# DAQ_IO.net
KiCad netlist of a schematic drawn in Altium Designer
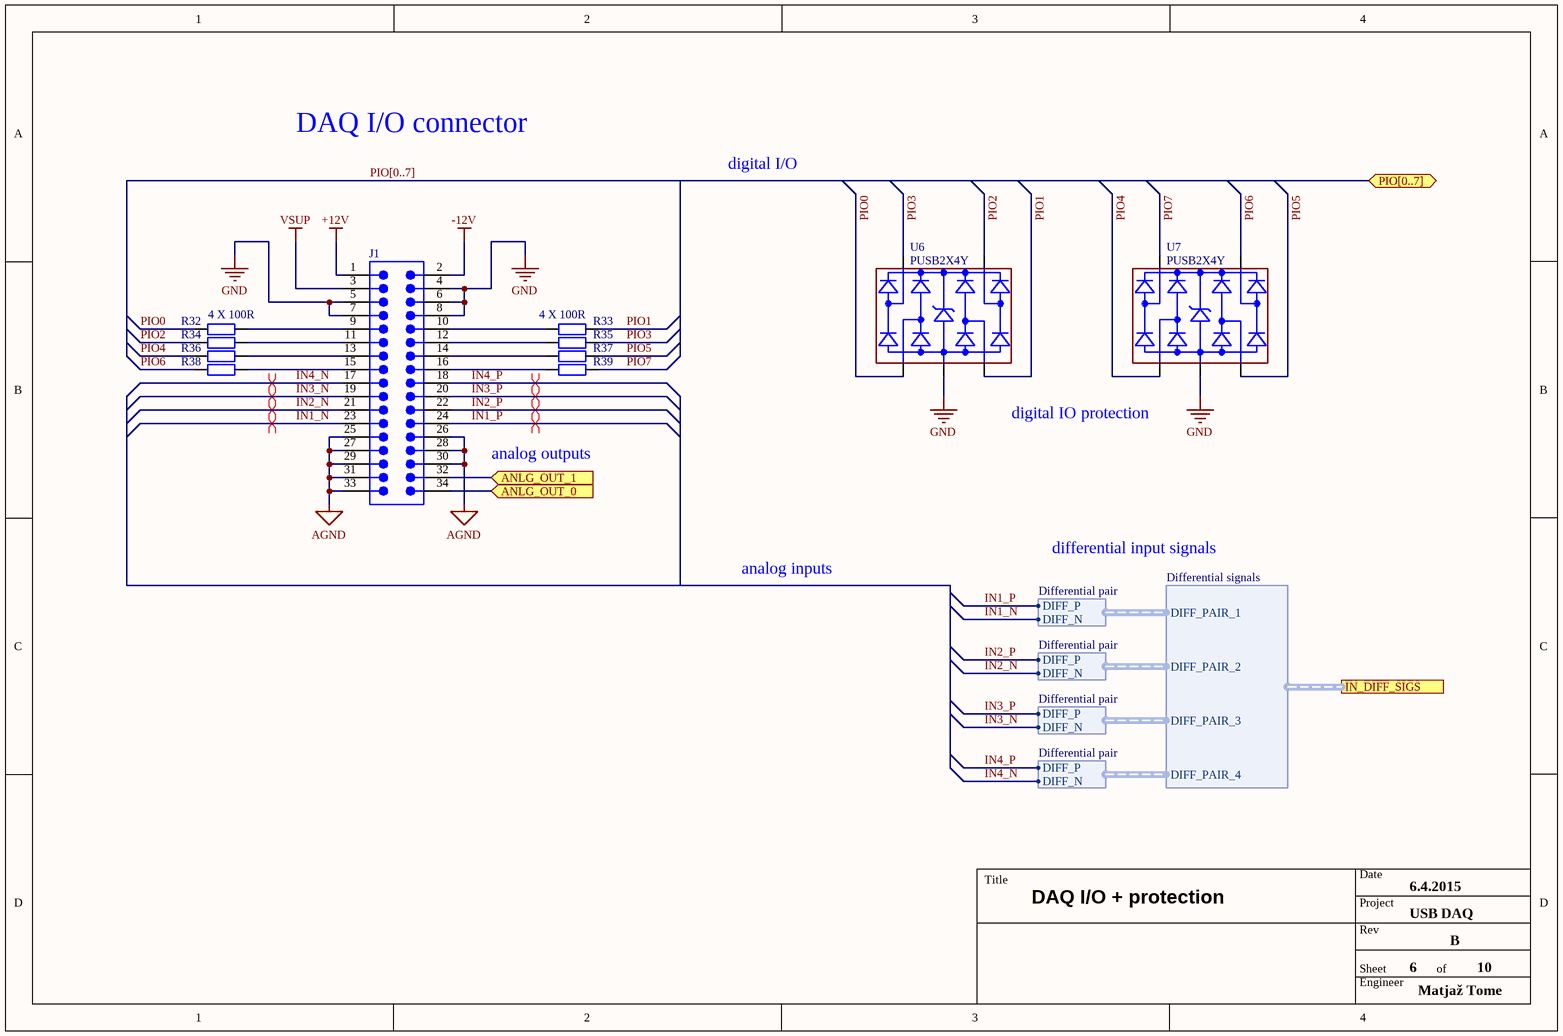
[diagram p0: DAQ_IO.SchDoc]

(export (version "E")
  (design (tool "Eeschema 10.0.6"))
  (components
    (comp (ref "J1")
      (value "2X17")
      (footprint "IDC34R")
      (description "Pin Header, Right Angle, Wire-to-Board, 2.54 mm, 2 Rows, 34 Contacts, Through Hole Right Angle")
      (fields (field (name "MANUFACTURER") "Harting"))
      (libsource (lib "DAQ_REV_B") (part "09 18 534 7323"))
    )
    (comp (ref "R32")
      (value "100R")
      (footprint "R_0603")
      (description "Generic resistor")
      (libsource (lib "DAQ_REV_B") (part "Resistor"))
    )
    (comp (ref "R33")
      (value "100R")
      (footprint "R_0603")
      (description "Generic resistor")
      (libsource (lib "DAQ_REV_B") (part "Resistor"))
    )
    (comp (ref "R34")
      (value "100R")
      (footprint "R_0603")
      (description "Generic resistor")
      (libsource (lib "DAQ_REV_B") (part "Resistor"))
    )
    (comp (ref "R35")
      (value "100R")
      (footprint "R_0603")
      (description "Generic resistor")
      (libsource (lib "DAQ_REV_B") (part "Resistor"))
    )
    (comp (ref "R36")
      (value "100R")
      (footprint "R_0603")
      (description "Generic resistor")
      (libsource (lib "DAQ_REV_B") (part "Resistor"))
    )
    (comp (ref "R37")
      (value "100R")
      (footprint "R_0603")
      (description "Generic resistor")
      (libsource (lib "DAQ_REV_B") (part "Resistor"))
    )
    (comp (ref "R38")
      (value "100R")
      (footprint "R_0603")
      (description "Generic resistor")
      (libsource (lib "DAQ_REV_B") (part "Resistor"))
    )
    (comp (ref "R39")
      (value "100R")
      (footprint "R_0603")
      (description "Generic resistor")
      (libsource (lib "DAQ_REV_B") (part "Resistor"))
    )
    (comp (ref "U6")
      (value "PUSB2X4Y")
      (footprint "SOT363")
      (description "ESD protection for high-speed interfaces")
      (fields (field (name "PART NUMBER") "XDE0000") (field (name "MANUFACTURER") "Multicomp"))
      (libsource (lib "DAQ_REV_B") (part "PUSB2X4Y"))
    )
    (comp (ref "U7")
      (value "PUSB2X4Y")
      (footprint "SOT363")
      (description "ESD protection for high-speed interfaces")
      (fields (field (name "PART NUMBER") "XDE0000") (field (name "MANUFACTURER") "Multicomp"))
      (libsource (lib "DAQ_REV_B") (part "PUSB2X4Y"))
    )
  )
  (nets
    (net (code "4") (name "+12V") (class "Default")
      (node (ref "J1") (pin "1") (pinfunction "1_1") (pintype "passive"))
    )
    (net (code "5") (name "-12V") (class "Default")
      (node (ref "J1") (pin "2") (pinfunction "2_2") (pintype "passive"))
    )
    (net (code "6") (name "/ANLG_OUT_0") (class "Default")
      (node (ref "J1") (pin "34") (pinfunction "34_34") (pintype "passive"))
    )
    (net (code "7") (name "/ANLG_OUT_1") (class "Default")
      (node (ref "J1") (pin "32") (pinfunction "32_32") (pintype "passive"))
    )
    (net (code "8") (name "/IN1_N") (class "Default")
      (node (ref "J1") (pin "23") (pinfunction "23_23") (pintype "passive"))
    )
    (net (code "9") (name "/IN1_P") (class "Default")
      (node (ref "J1") (pin "24") (pinfunction "24_24") (pintype "passive"))
    )
    (net (code "10") (name "/IN2_N") (class "Default")
      (node (ref "J1") (pin "21") (pinfunction "21_21") (pintype "passive"))
    )
    (net (code "11") (name "/IN2_P") (class "Default")
      (node (ref "J1") (pin "22") (pinfunction "22_22") (pintype "passive"))
    )
    (net (code "12") (name "/IN3_N") (class "Default")
      (node (ref "J1") (pin "19") (pinfunction "19_19") (pintype "passive"))
    )
    (net (code "13") (name "/IN3_P") (class "Default")
      (node (ref "J1") (pin "20") (pinfunction "20_20") (pintype "passive"))
    )
    (net (code "14") (name "/IN4_N") (class "Default")
      (node (ref "J1") (pin "17") (pinfunction "17_17") (pintype "passive"))
    )
    (net (code "15") (name "/IN4_P") (class "Default")
      (node (ref "J1") (pin "18") (pinfunction "18_18") (pintype "passive"))
    )
    (net (code "16") (name "/PIO0") (class "Default")
      (node (ref "R32") (pin "1") (pintype "passive"))
      (node (ref "U6") (pin "1") (pinfunction "1_1") (pintype "passive"))
    )
    (net (code "17") (name "/PIO1") (class "Default")
      (node (ref "R33") (pin "2") (pintype "passive"))
      (node (ref "U6") (pin "3") (pinfunction "3_3") (pintype "passive"))
    )
    (net (code "18") (name "/PIO2") (class "Default")
      (node (ref "R34") (pin "1") (pintype "passive"))
      (node (ref "U6") (pin "4") (pinfunction "4_4") (pintype "passive"))
    )
    (net (code "19") (name "/PIO3") (class "Default")
      (node (ref "R35") (pin "2") (pintype "passive"))
      (node (ref "U6") (pin "6") (pinfunction "6_6") (pintype "passive"))
    )
    (net (code "20") (name "/PIO4") (class "Default")
      (node (ref "R36") (pin "1") (pintype "passive"))
      (node (ref "U7") (pin "1") (pinfunction "1_1") (pintype "passive"))
    )
    (net (code "21") (name "/PIO5") (class "Default")
      (node (ref "R37") (pin "2") (pintype "passive"))
      (node (ref "U7") (pin "3") (pinfunction "3_3") (pintype "passive"))
    )
    (net (code "22") (name "/PIO6") (class "Default")
      (node (ref "R38") (pin "1") (pintype "passive"))
      (node (ref "U7") (pin "4") (pinfunction "4_4") (pintype "passive"))
    )
    (net (code "23") (name "/PIO7") (class "Default")
      (node (ref "R39") (pin "2") (pintype "passive"))
      (node (ref "U7") (pin "6") (pinfunction "6_6") (pintype "passive"))
    )
    (net (code "27") (name "AGND") (class "Default")
      (node (ref "J1") (pin "25") (pinfunction "25_25") (pintype "passive"))
      (node (ref "J1") (pin "26") (pinfunction "26_26") (pintype "passive"))
      (node (ref "J1") (pin "27") (pinfunction "27_27") (pintype "passive"))
      (node (ref "J1") (pin "28") (pinfunction "28_28") (pintype "passive"))
      (node (ref "J1") (pin "29") (pinfunction "29_29") (pintype "passive"))
      (node (ref "J1") (pin "30") (pinfunction "30_30") (pintype "passive"))
      (node (ref "J1") (pin "31") (pinfunction "31_31") (pintype "passive"))
      (node (ref "J1") (pin "33") (pinfunction "33_33") (pintype "passive"))
    )
    (net (code "28") (name "GND") (class "Default")
      (node (ref "J1") (pin "4") (pinfunction "4_4") (pintype "passive"))
      (node (ref "J1") (pin "5") (pinfunction "5_5") (pintype "passive"))
      (node (ref "J1") (pin "6") (pinfunction "6_6") (pintype "passive"))
      (node (ref "J1") (pin "7") (pinfunction "7_7") (pintype "passive"))
      (node (ref "J1") (pin "8") (pinfunction "8_8") (pintype "passive"))
      (node (ref "U6") (pin "2") (pinfunction "2_2") (pintype "passive"))
      (node (ref "U7") (pin "2") (pinfunction "2_2") (pintype "passive"))
    )
    (net (code "29") (name "Net-(J1-Pad9)") (class "Default")
      (node (ref "J1") (pin "9") (pinfunction "9_9") (pintype "passive"))
      (node (ref "R32") (pin "2") (pintype "passive"))
    )
    (net (code "30") (name "Net-(J1-Pad10)") (class "Default")
      (node (ref "J1") (pin "10") (pinfunction "10_10") (pintype "passive"))
      (node (ref "R33") (pin "1") (pintype "passive"))
    )
    (net (code "31") (name "Net-(J1-Pad11)") (class "Default")
      (node (ref "J1") (pin "11") (pinfunction "11_11") (pintype "passive"))
      (node (ref "R34") (pin "2") (pintype "passive"))
    )
    (net (code "32") (name "Net-(J1-Pad12)") (class "Default")
      (node (ref "J1") (pin "12") (pinfunction "12_12") (pintype "passive"))
      (node (ref "R35") (pin "1") (pintype "passive"))
    )
    (net (code "33") (name "Net-(J1-Pad13)") (class "Default")
      (node (ref "J1") (pin "13") (pinfunction "13_13") (pintype "passive"))
      (node (ref "R36") (pin "2") (pintype "passive"))
    )
    (net (code "34") (name "Net-(J1-Pad14)") (class "Default")
      (node (ref "J1") (pin "14") (pinfunction "14_14") (pintype "passive"))
      (node (ref "R37") (pin "1") (pintype "passive"))
    )
    (net (code "35") (name "Net-(J1-Pad15)") (class "Default")
      (node (ref "J1") (pin "15") (pinfunction "15_15") (pintype "passive"))
      (node (ref "R38") (pin "2") (pintype "passive"))
    )
    (net (code "36") (name "Net-(J1-Pad16)") (class "Default")
      (node (ref "J1") (pin "16") (pinfunction "16_16") (pintype "passive"))
      (node (ref "R39") (pin "1") (pintype "passive"))
    )
    (net (code "37") (name "VSUP") (class "Default")
      (node (ref "J1") (pin "3") (pinfunction "3_3") (pintype "passive"))
    )
  )
)
